# hdmi.net
KiCad netlist of a schematic drawn in Altium Designer
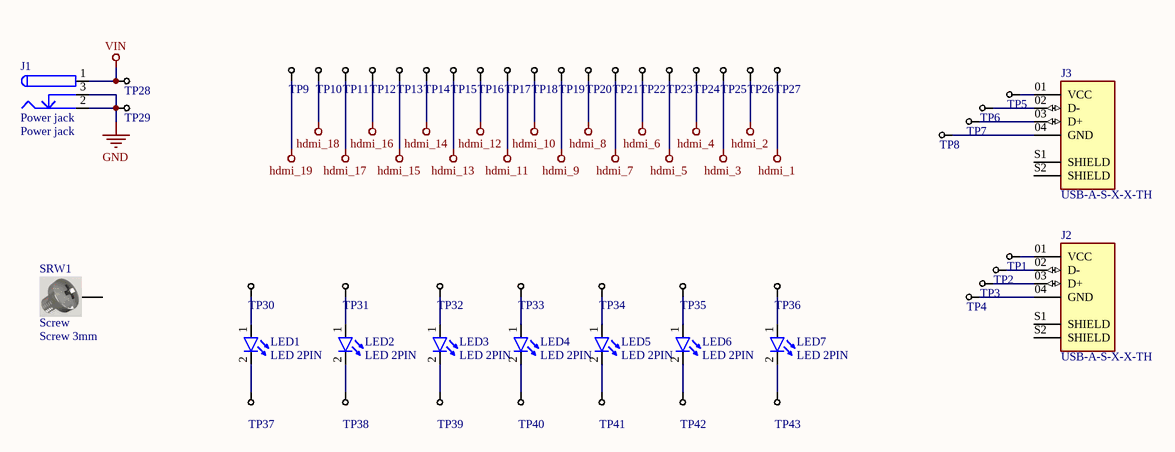
[diagram p0: hdmi.SchDoc]

(export (version "E")
  (design (tool "Eeschema 10.0.6"))
  (components
    (comp (ref "J1")
      (value "Power jack")
      (footprint "Power Jack")
      (fields (field (name "ALTIUM_UNNAMED_1") "Power jack"))
      (libsource (lib "3D LIB") (part "Power jack"))
    )
    (comp (ref "J2")
      (value "USB-A-S-X-X-TH")
      (footprint "SAMTEC_USB-A-S-X-X-TH")
      (description "USB-A (USB TYPE-A) USB 2.0 Receptacle Connector 4 Position Through Hole, Right Angle")
      (fields (field (name "MP") "USB-A-S-S-W-TH") (field (name "DIGI-KEY_PART_NUMBER") "SAM10373-ND"))
      (libsource (lib "SnapEDAsch") (part "USB-A-S-X-X-TH"))
    )
    (comp (ref "J3")
      (value "USB-A-S-X-X-TH")
      (footprint "SAMTEC_USB-A-S-X-X-TH")
      (description "USB-A (USB TYPE-A) USB 2.0 Receptacle Connector 4 Position Through Hole, Right Angle")
      (fields (field (name "MP") "USB-A-S-S-W-TH") (field (name "DIGI-KEY_PART_NUMBER") "SAM10373-ND"))
      (libsource (lib "SnapEDAsch") (part "USB-A-S-X-X-TH"))
    )
    (comp (ref "LED1") (value "LED 2PIN") (footprint "LED 5mm") (libsource (lib "3D LIB") (part "LED 2PIN")))
    (comp (ref "LED2") (value "LED 2PIN") (footprint "LED 5mm") (libsource (lib "3D LIB") (part "LED 2PIN")))
    (comp (ref "LED3") (value "LED 2PIN") (footprint "LED 5mm") (libsource (lib "3D LIB") (part "LED 2PIN")))
    (comp (ref "LED4") (value "LED 2PIN") (footprint "LED 5mm") (libsource (lib "3D LIB") (part "LED 2PIN")))
    (comp (ref "LED5") (value "LED 2PIN") (footprint "LED 5mm") (libsource (lib "3D LIB") (part "LED 2PIN")))
    (comp (ref "LED6") (value "LED 2PIN") (footprint "LED 5mm") (libsource (lib "3D LIB") (part "LED 2PIN")))
    (comp (ref "LED7") (value "LED 2PIN") (footprint "LED 5mm") (libsource (lib "3D LIB") (part "LED 2PIN")))
    (comp (ref "SRW1")
      (value "Screw")
      (footprint "mini hdmi socket")
      (fields (field (name "ALTIUM_UNNAMED_1") "Screw 3mm"))
      (libsource (lib "3D LIB") (part "Screw"))
    )
    (comp (ref "TP1")
      (value "TEST POINT")
      (footprint "Test Point On Top")
      (libsource (lib "3D LIB") (part "TEST POINT"))
    )
    (comp (ref "TP2")
      (value "TEST POINT")
      (footprint "Test Point On Top")
      (libsource (lib "3D LIB") (part "TEST POINT"))
    )
    (comp (ref "TP3")
      (value "TEST POINT")
      (footprint "Test Point On Top")
      (libsource (lib "3D LIB") (part "TEST POINT"))
    )
    (comp (ref "TP4")
      (value "TEST POINT")
      (footprint "Test Point On Top")
      (libsource (lib "3D LIB") (part "TEST POINT"))
    )
    (comp (ref "TP5")
      (value "TEST POINT")
      (footprint "Test Point On Top")
      (libsource (lib "3D LIB") (part "TEST POINT"))
    )
    (comp (ref "TP6")
      (value "TEST POINT")
      (footprint "Test Point On Top")
      (libsource (lib "3D LIB") (part "TEST POINT"))
    )
    (comp (ref "TP7")
      (value "TEST POINT")
      (footprint "Test Point On Top")
      (libsource (lib "3D LIB") (part "TEST POINT"))
    )
    (comp (ref "TP8")
      (value "TEST POINT")
      (footprint "Test Point On Top")
      (libsource (lib "3D LIB") (part "TEST POINT"))
    )
    (comp (ref "TP9")
      (value "TEST POINT")
      (footprint "Test Point On Top")
      (libsource (lib "3D LIB") (part "TEST POINT"))
    )
    (comp (ref "TP10")
      (value "TEST POINT")
      (footprint "Test Point On Top")
      (libsource (lib "3D LIB") (part "TEST POINT"))
    )
    (comp (ref "TP11")
      (value "TEST POINT")
      (footprint "Test Point On Top")
      (libsource (lib "3D LIB") (part "TEST POINT"))
    )
    (comp (ref "TP12")
      (value "TEST POINT")
      (footprint "Test Point On Top")
      (libsource (lib "3D LIB") (part "TEST POINT"))
    )
    (comp (ref "TP13")
      (value "TEST POINT")
      (footprint "Test Point On Top")
      (libsource (lib "3D LIB") (part "TEST POINT"))
    )
    (comp (ref "TP14")
      (value "TEST POINT")
      (footprint "Test Point On Top")
      (libsource (lib "3D LIB") (part "TEST POINT"))
    )
    (comp (ref "TP15")
      (value "TEST POINT")
      (footprint "Test Point On Top")
      (libsource (lib "3D LIB") (part "TEST POINT"))
    )
    (comp (ref "TP16")
      (value "TEST POINT")
      (footprint "Test Point On Top")
      (libsource (lib "3D LIB") (part "TEST POINT"))
    )
    (comp (ref "TP17")
      (value "TEST POINT")
      (footprint "Test Point On Top")
      (libsource (lib "3D LIB") (part "TEST POINT"))
    )
    (comp (ref "TP18")
      (value "TEST POINT")
      (footprint "Test Point On Top")
      (libsource (lib "3D LIB") (part "TEST POINT"))
    )
    (comp (ref "TP19")
      (value "TEST POINT")
      (footprint "Test Point On Top")
      (libsource (lib "3D LIB") (part "TEST POINT"))
    )
    (comp (ref "TP20")
      (value "TEST POINT")
      (footprint "Test Point On Top")
      (libsource (lib "3D LIB") (part "TEST POINT"))
    )
    (comp (ref "TP21")
      (value "TEST POINT")
      (footprint "Test Point On Top")
      (libsource (lib "3D LIB") (part "TEST POINT"))
    )
    (comp (ref "TP22")
      (value "TEST POINT")
      (footprint "Test Point On Top")
      (libsource (lib "3D LIB") (part "TEST POINT"))
    )
    (comp (ref "TP23")
      (value "TEST POINT")
      (footprint "Test Point On Top")
      (libsource (lib "3D LIB") (part "TEST POINT"))
    )
    (comp (ref "TP24")
      (value "TEST POINT")
      (footprint "Test Point On Top")
      (libsource (lib "3D LIB") (part "TEST POINT"))
    )
    (comp (ref "TP25")
      (value "TEST POINT")
      (footprint "Test Point On Top")
      (libsource (lib "3D LIB") (part "TEST POINT"))
    )
    (comp (ref "TP26")
      (value "TEST POINT")
      (footprint "Test Point On Top")
      (libsource (lib "3D LIB") (part "TEST POINT"))
    )
    (comp (ref "TP27")
      (value "TEST POINT")
      (footprint "Test Point On Top")
      (libsource (lib "3D LIB") (part "TEST POINT"))
    )
    (comp (ref "TP28")
      (value "TEST POINT")
      (footprint "Test Point On Top")
      (libsource (lib "3D LIB") (part "TEST POINT"))
    )
    (comp (ref "TP29")
      (value "TEST POINT")
      (footprint "Test Point On Top")
      (libsource (lib "3D LIB") (part "TEST POINT"))
    )
    (comp (ref "TP30")
      (value "TEST POINT")
      (footprint "Test Point On Top")
      (libsource (lib "3D LIB") (part "TEST POINT"))
    )
    (comp (ref "TP31")
      (value "TEST POINT")
      (footprint "Test Point On Top")
      (libsource (lib "3D LIB") (part "TEST POINT"))
    )
    (comp (ref "TP32")
      (value "TEST POINT")
      (footprint "Test Point On Top")
      (libsource (lib "3D LIB") (part "TEST POINT"))
    )
    (comp (ref "TP33")
      (value "TEST POINT")
      (footprint "Test Point On Top")
      (libsource (lib "3D LIB") (part "TEST POINT"))
    )
    (comp (ref "TP34")
      (value "TEST POINT")
      (footprint "Test Point On Top")
      (libsource (lib "3D LIB") (part "TEST POINT"))
    )
    (comp (ref "TP35")
      (value "TEST POINT")
      (footprint "Test Point On Top")
      (libsource (lib "3D LIB") (part "TEST POINT"))
    )
    (comp (ref "TP36")
      (value "TEST POINT")
      (footprint "Test Point On Top")
      (libsource (lib "3D LIB") (part "TEST POINT"))
    )
    (comp (ref "TP37")
      (value "TEST POINT")
      (footprint "Test Point On Top")
      (libsource (lib "3D LIB") (part "TEST POINT"))
    )
    (comp (ref "TP38")
      (value "TEST POINT")
      (footprint "Test Point On Top")
      (libsource (lib "3D LIB") (part "TEST POINT"))
    )
    (comp (ref "TP39")
      (value "TEST POINT")
      (footprint "Test Point On Top")
      (libsource (lib "3D LIB") (part "TEST POINT"))
    )
    (comp (ref "TP40")
      (value "TEST POINT")
      (footprint "Test Point On Top")
      (libsource (lib "3D LIB") (part "TEST POINT"))
    )
    (comp (ref "TP41")
      (value "TEST POINT")
      (footprint "Test Point On Top")
      (libsource (lib "3D LIB") (part "TEST POINT"))
    )
    (comp (ref "TP42")
      (value "TEST POINT")
      (footprint "Test Point On Top")
      (libsource (lib "3D LIB") (part "TEST POINT"))
    )
    (comp (ref "TP43")
      (value "TEST POINT")
      (footprint "Test Point On Top")
      (libsource (lib "3D LIB") (part "TEST POINT"))
    )
  )
  (nets
    (net (code "1") (name "GND") (class "Default")
      (node (ref "J1") (pin "2") (pinfunction "2_2") (pintype "power_in"))
      (node (ref "J1") (pin "3") (pinfunction "3_3") (pintype "power_in"))
      (node (ref "TP29") (pin "1") (pinfunction "T_1") (pintype "passive"))
    )
    (net (code "2") (name "Net-(J2-D+)") (class "Default")
      (node (ref "J2") (pin "03") (pinfunction "D+_03") (pintype "bidirectional"))
      (node (ref "TP3") (pin "1") (pinfunction "T_1") (pintype "passive"))
    )
    (net (code "3") (name "Net-(J2-D-)") (class "Default")
      (node (ref "J2") (pin "02") (pinfunction "D-_02") (pintype "bidirectional"))
      (node (ref "TP2") (pin "1") (pinfunction "T_1") (pintype "passive"))
    )
    (net (code "4") (name "Net-(J2-GND)") (class "Default")
      (node (ref "J2") (pin "04") (pinfunction "GND_04") (pintype "power_in"))
      (node (ref "TP4") (pin "1") (pinfunction "T_1") (pintype "passive"))
    )
    (net (code "5") (name "Net-(J2-VCC)") (class "Default")
      (node (ref "J2") (pin "01") (pinfunction "VCC_01") (pintype "power_in"))
      (node (ref "TP1") (pin "1") (pinfunction "T_1") (pintype "passive"))
    )
    (net (code "6") (name "Net-(J3-D+)") (class "Default")
      (node (ref "J3") (pin "03") (pinfunction "D+_03") (pintype "bidirectional"))
      (node (ref "TP7") (pin "1") (pinfunction "T_1") (pintype "passive"))
    )
    (net (code "7") (name "Net-(J3-D-)") (class "Default")
      (node (ref "J3") (pin "02") (pinfunction "D-_02") (pintype "bidirectional"))
      (node (ref "TP6") (pin "1") (pinfunction "T_1") (pintype "passive"))
    )
    (net (code "8") (name "Net-(J3-GND)") (class "Default")
      (node (ref "J3") (pin "04") (pinfunction "GND_04") (pintype "power_in"))
      (node (ref "TP8") (pin "1") (pinfunction "T_1") (pintype "passive"))
    )
    (net (code "9") (name "Net-(J3-VCC)") (class "Default")
      (node (ref "J3") (pin "01") (pinfunction "VCC_01") (pintype "power_in"))
      (node (ref "TP5") (pin "1") (pinfunction "T_1") (pintype "passive"))
    )
    (net (code "10") (name "Net-(LED1-A)") (class "Default")
      (node (ref "LED1") (pin "1") (pinfunction "A_1") (pintype "passive"))
      (node (ref "TP30") (pin "1") (pinfunction "T_1") (pintype "passive"))
    )
    (net (code "11") (name "Net-(LED1-K)") (class "Default")
      (node (ref "LED1") (pin "2") (pinfunction "K_2") (pintype "passive"))
      (node (ref "TP37") (pin "1") (pinfunction "T_1") (pintype "passive"))
    )
    (net (code "12") (name "Net-(LED2-A)") (class "Default")
      (node (ref "LED2") (pin "1") (pinfunction "A_1") (pintype "passive"))
      (node (ref "TP31") (pin "1") (pinfunction "T_1") (pintype "passive"))
    )
    (net (code "13") (name "Net-(LED2-K)") (class "Default")
      (node (ref "LED2") (pin "2") (pinfunction "K_2") (pintype "passive"))
      (node (ref "TP38") (pin "1") (pinfunction "T_1") (pintype "passive"))
    )
    (net (code "14") (name "Net-(LED3-A)") (class "Default")
      (node (ref "LED3") (pin "1") (pinfunction "A_1") (pintype "passive"))
      (node (ref "TP32") (pin "1") (pinfunction "T_1") (pintype "passive"))
    )
    (net (code "15") (name "Net-(LED3-K)") (class "Default")
      (node (ref "LED3") (pin "2") (pinfunction "K_2") (pintype "passive"))
      (node (ref "TP39") (pin "1") (pinfunction "T_1") (pintype "passive"))
    )
    (net (code "16") (name "Net-(LED4-A)") (class "Default")
      (node (ref "LED4") (pin "1") (pinfunction "A_1") (pintype "passive"))
      (node (ref "TP33") (pin "1") (pinfunction "T_1") (pintype "passive"))
    )
    (net (code "17") (name "Net-(LED4-K)") (class "Default")
      (node (ref "LED4") (pin "2") (pinfunction "K_2") (pintype "passive"))
      (node (ref "TP40") (pin "1") (pinfunction "T_1") (pintype "passive"))
    )
    (net (code "18") (name "Net-(LED5-A)") (class "Default")
      (node (ref "LED5") (pin "1") (pinfunction "A_1") (pintype "passive"))
      (node (ref "TP34") (pin "1") (pinfunction "T_1") (pintype "passive"))
    )
    (net (code "19") (name "Net-(LED5-K)") (class "Default")
      (node (ref "LED5") (pin "2") (pinfunction "K_2") (pintype "passive"))
      (node (ref "TP41") (pin "1") (pinfunction "T_1") (pintype "passive"))
    )
    (net (code "20") (name "Net-(LED6-A)") (class "Default")
      (node (ref "LED6") (pin "1") (pinfunction "A_1") (pintype "passive"))
      (node (ref "TP35") (pin "1") (pinfunction "T_1") (pintype "passive"))
    )
    (net (code "21") (name "Net-(LED6-K)") (class "Default")
      (node (ref "LED6") (pin "2") (pinfunction "K_2") (pintype "passive"))
      (node (ref "TP42") (pin "1") (pinfunction "T_1") (pintype "passive"))
    )
    (net (code "22") (name "Net-(LED7-A)") (class "Default")
      (node (ref "LED7") (pin "1") (pinfunction "A_1") (pintype "passive"))
      (node (ref "TP36") (pin "1") (pinfunction "T_1") (pintype "passive"))
    )
    (net (code "23") (name "Net-(LED7-K)") (class "Default")
      (node (ref "LED7") (pin "2") (pinfunction "K_2") (pintype "passive"))
      (node (ref "TP43") (pin "1") (pinfunction "T_1") (pintype "passive"))
    )
    (net (code "24") (name "VIN") (class "Default")
      (node (ref "J1") (pin "1") (pinfunction "1_1") (pintype "power_in"))
      (node (ref "TP28") (pin "1") (pinfunction "T_1") (pintype "passive"))
    )
    (net (code "25") (name "hdmi_1") (class "Default")
      (node (ref "TP27") (pin "1") (pinfunction "T_1") (pintype "passive"))
    )
    (net (code "26") (name "hdmi_2") (class "Default")
      (node (ref "TP26") (pin "1") (pinfunction "T_1") (pintype "passive"))
    )
    (net (code "27") (name "hdmi_3") (class "Default")
      (node (ref "TP25") (pin "1") (pinfunction "T_1") (pintype "passive"))
    )
    (net (code "28") (name "hdmi_4") (class "Default")
      (node (ref "TP24") (pin "1") (pinfunction "T_1") (pintype "passive"))
    )
    (net (code "29") (name "hdmi_5") (class "Default")
      (node (ref "TP23") (pin "1") (pinfunction "T_1") (pintype "passive"))
    )
    (net (code "30") (name "hdmi_6") (class "Default")
      (node (ref "TP22") (pin "1") (pinfunction "T_1") (pintype "passive"))
    )
    (net (code "31") (name "hdmi_7") (class "Default")
      (node (ref "TP21") (pin "1") (pinfunction "T_1") (pintype "passive"))
    )
    (net (code "32") (name "hdmi_8") (class "Default")
      (node (ref "TP20") (pin "1") (pinfunction "T_1") (pintype "passive"))
    )
    (net (code "33") (name "hdmi_9") (class "Default")
      (node (ref "TP19") (pin "1") (pinfunction "T_1") (pintype "passive"))
    )
    (net (code "34") (name "hdmi_10") (class "Default")
      (node (ref "TP18") (pin "1") (pinfunction "T_1") (pintype "passive"))
    )
    (net (code "35") (name "hdmi_11") (class "Default")
      (node (ref "TP17") (pin "1") (pinfunction "T_1") (pintype "passive"))
    )
    (net (code "36") (name "hdmi_12") (class "Default")
      (node (ref "TP16") (pin "1") (pinfunction "T_1") (pintype "passive"))
    )
    (net (code "37") (name "hdmi_13") (class "Default")
      (node (ref "TP15") (pin "1") (pinfunction "T_1") (pintype "passive"))
    )
    (net (code "38") (name "hdmi_14") (class "Default")
      (node (ref "TP14") (pin "1") (pinfunction "T_1") (pintype "passive"))
    )
    (net (code "39") (name "hdmi_15") (class "Default")
      (node (ref "TP13") (pin "1") (pinfunction "T_1") (pintype "passive"))
    )
    (net (code "40") (name "hdmi_16") (class "Default")
      (node (ref "TP12") (pin "1") (pinfunction "T_1") (pintype "passive"))
    )
    (net (code "41") (name "hdmi_17") (class "Default")
      (node (ref "TP11") (pin "1") (pinfunction "T_1") (pintype "passive"))
    )
    (net (code "42") (name "hdmi_18") (class "Default")
      (node (ref "TP10") (pin "1") (pinfunction "T_1") (pintype "passive"))
    )
    (net (code "43") (name "hdmi_19") (class "Default")
      (node (ref "TP9") (pin "1") (pinfunction "T_1") (pintype "passive"))
    )
    (net (code "44") (name "unconnected-(J2-SHIELD-PadS1)") (class "Default")
      (node (ref "J2") (pin "S1") (pinfunction "SHIELD_S1") (pintype "passive"))
    )
    (net (code "45") (name "unconnected-(J2-SHIELD-PadS2)") (class "Default")
      (node (ref "J2") (pin "S2") (pinfunction "SHIELD_S2") (pintype "passive"))
    )
    (net (code "46") (name "unconnected-(J3-SHIELD-PadS1)") (class "Default")
      (node (ref "J3") (pin "S1") (pinfunction "SHIELD_S1") (pintype "passive"))
    )
    (net (code "47") (name "unconnected-(J3-SHIELD-PadS2)") (class "Default")
      (node (ref "J3") (pin "S2") (pinfunction "SHIELD_S2") (pintype "passive"))
    )
    (net (code "48") (name "unconnected-(SRW1-S-Pad1)") (class "Default")
      (node (ref "SRW1") (pin "1") (pinfunction "S_1") (pintype "passive"))
    )
  )
)
